# DM1092_IMU.net
KiCad netlist of a schematic drawn in Altium Designer
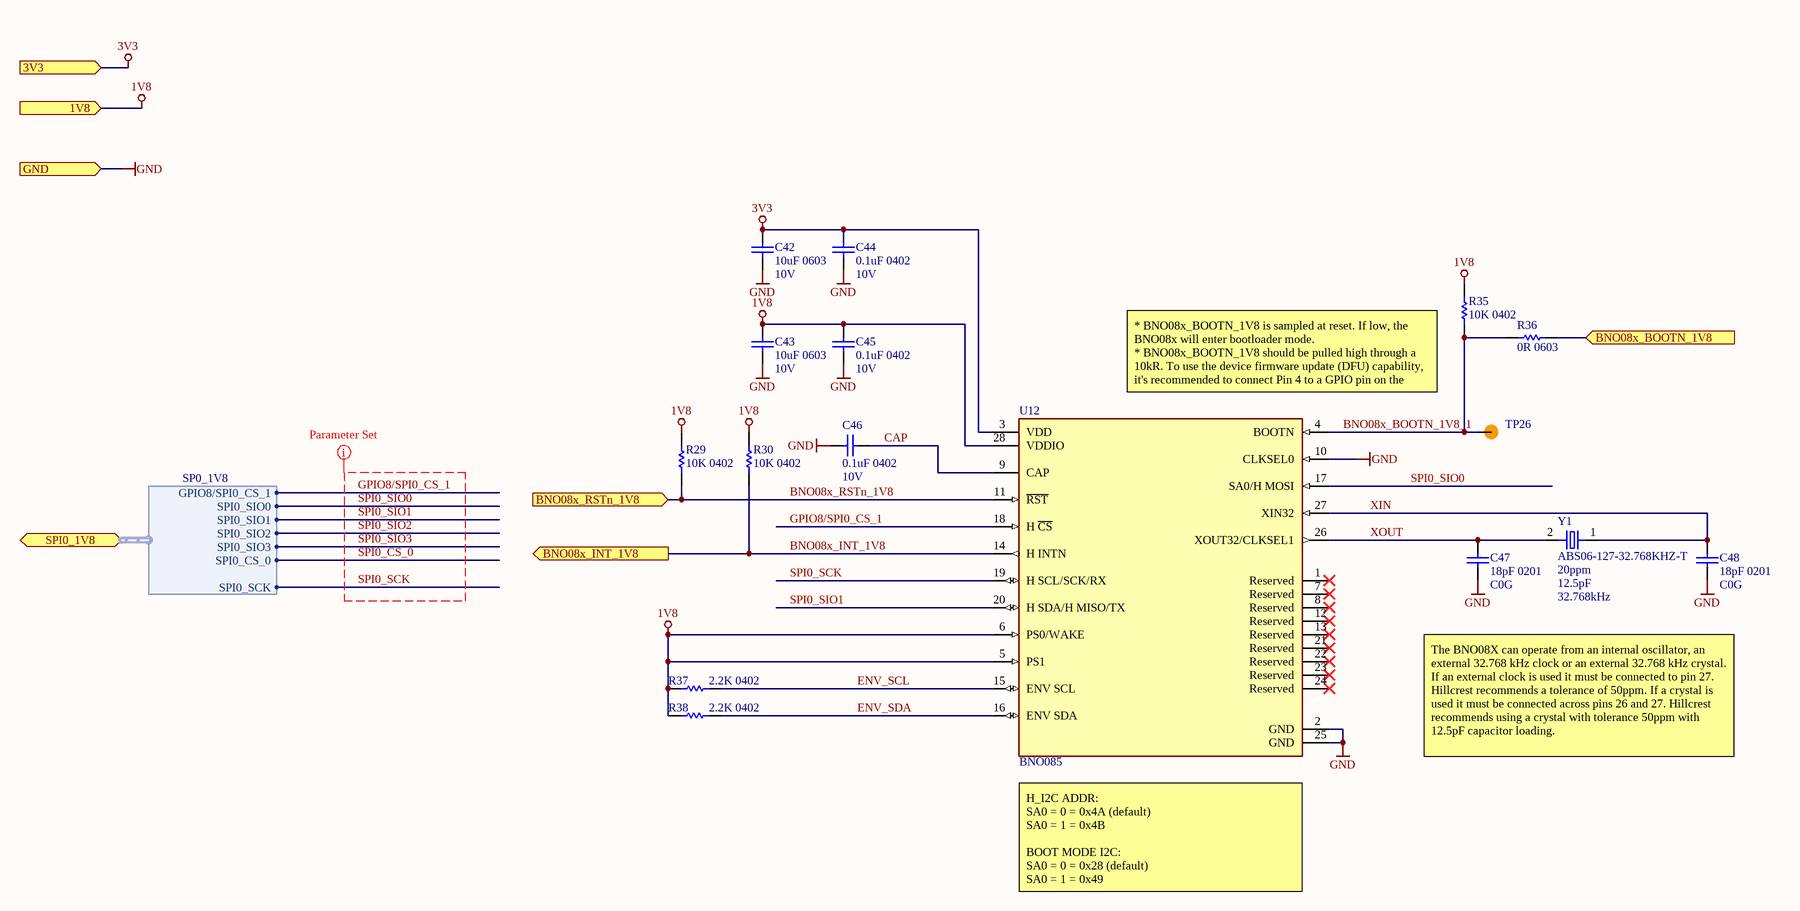
[diagram p0: DM1092_IMU.SchDoc]

(export (version "E")
  (design (tool "Eeschema 10.0.6"))
  (components
    (comp (ref "C42")
      (value "10uF 0603")
      (footprint "CAP_Altium_Vault_Generic:CAPC0603(1608)100_N")
      (description "CAP CER 10UF 10V X5R 0603 20%")
      (fields (field (name "TOLERANCE") "20%") (field (name "VOLTAGE RATING") "10V"))
      (libsource (lib "LuxonisMaster") (part "GRM188R61A106ME69D"))
    )
    (comp (ref "C43")
      (value "10uF 0603")
      (footprint "CAP_Altium_Vault_Generic:CAPC0603(1608)100_N")
      (description "CAP CER 10UF 10V X5R 0603 20%")
      (fields (field (name "TOLERANCE") "20%") (field (name "VOLTAGE RATING") "10V"))
      (libsource (lib "LuxonisMaster") (part "GRM188R61A106ME69D"))
    )
    (comp (ref "C44")
      (value "0.1uF 0402")
      (footprint "CAP_Altium_Vault_Generic:CAPC0402(1005)70_N")
      (description "CAP CER 0.1UF 10V X7R 0402 5%")
      (fields (field (name "TOLERANCE") "5%") (field (name "VOLTAGE RATING") "10V"))
      (libsource (lib "LuxonisMaster") (part "GRM155R71A104JA01D"))
    )
    (comp (ref "C45")
      (value "0.1uF 0402")
      (footprint "CAP_Altium_Vault_Generic:CAPC0402(1005)70_N")
      (description "CAP CER 0.1UF 10V X7R 0402 5%")
      (fields (field (name "TOLERANCE") "5%") (field (name "VOLTAGE RATING") "10V"))
      (libsource (lib "LuxonisMaster") (part "GRM155R71A104JA01D"))
    )
    (comp (ref "C46")
      (value "0.1uF 0402")
      (footprint "CAP_Altium_Vault_Generic:CAPC0402(1005)70_N")
      (description "CAP CER 0.1UF 10V X7R 0402 5%")
      (fields (field (name "TOLERANCE") "5%") (field (name "VOLTAGE RATING") "10V"))
      (libsource (lib "LuxonisMaster") (part "GRM155R71A104JA01D"))
    )
    (comp (ref "C47")
      (value "18pF 0201")
      (footprint "CAP_Altium_Vault_Generic:CAPC0201(0603)33_N")
      (description "Cap Ceramic 18pF 25V C0G 1% Pad SMD 0201 125C T/R")
      (fields (field (name "TOLERANCE") "1%") (field (name "DIELECTRIC") "C0G"))
      (libsource (lib "DM1092_R0M0E0") (part "GRM0335C1E180FA01D"))
    )
    (comp (ref "C48")
      (value "18pF 0201")
      (footprint "CAP_Altium_Vault_Generic:CAPC0201(0603)33_N")
      (description "Cap Ceramic 18pF 25V C0G 1% Pad SMD 0201 125C T/R")
      (fields (field (name "TOLERANCE") "1%") (field (name "DIELECTRIC") "C0G"))
      (libsource (lib "DM1092_R0M0E0") (part "GRM0335C1E180FA01D"))
    )
    (comp (ref "R29")
      (value "10K 0402")
      (footprint "RES_Altium_Vault_Generic:RESC0402(1005)_N")
      (fields (field (name "TOLERANCE") "1%"))
      (libsource (lib "LuxonisMaster") (part "RC0402FR-1310KL"))
    )
    (comp (ref "R30")
      (value "10K 0402")
      (footprint "RES_Altium_Vault_Generic:RESC0402(1005)_N")
      (fields (field (name "TOLERANCE") "1%"))
      (libsource (lib "LuxonisMaster") (part "RC0402FR-1310KL"))
    )
    (comp (ref "R35")
      (value "10K 0402")
      (footprint "RES_Altium_Vault_Generic:RESC0402(1005)_N")
      (fields (field (name "TOLERANCE") "1%"))
      (libsource (lib "LuxonisMaster") (part "RC0402FR-1310KL"))
    )
    (comp (ref "R36")
      (value "0R 0603")
      (footprint "RES_Altium_Vault_Generic:RESC0603(1608)_N")
      (fields (field (name "TOLERANCE") "5%"))
      (libsource (lib "LuxonisMaster") (part "CRCW06030000Z0EA"))
    )
    (comp (ref "R37")
      (value "2.2K 0402")
      (footprint "RES_Altium_Vault_Generic:RESC0402(1005)_N")
      (description "RES SMD 2.2K OHM 1% 1/16W 0402")
      (fields (field (name "TOLERANCE") "1%"))
      (libsource (lib "LuxonisMaster") (part "RC0402FR-072K2L"))
    )
    (comp (ref "R38")
      (value "2.2K 0402")
      (footprint "RES_Altium_Vault_Generic:RESC0402(1005)_N")
      (description "RES SMD 2.2K OHM 1% 1/16W 0402")
      (fields (field (name "TOLERANCE") "1%"))
      (libsource (lib "LuxonisMaster") (part "RC0402FR-072K2L"))
    )
    (comp (ref "TP26")
      (value "TP100_200_NS")
      (footprint "LuxonisMaster:TP100_200_NS")
      (libsource (lib "LuxonisMaster") (part "TEST_POINT"))
    )
    (comp (ref "U12")
      (value "BNO085")
      (footprint "BW1092_R0M0E0:BNO085")
      (description "IMU ACCEL/GYRO/MAG I2C 32BIT")
      (libsource (lib "DM1092_R0M0E0") (part "BNO085"))
    )
    (comp (ref "Y1")
      (value "ABS06-127-32.768KHZ-T")
      (footprint "BW1092_R0M0E0:ABS06-127-32.768KHZ-T")
      (description "CRYSTAL 32.768kHz ±20ppm Crystal 12.5pF 90 kOhms 2-SMD, No Lead")
      (fields
        (field (name "FREQUENCY TOLERANCE") "20ppm")
        (field (name "LOAD CAPACITANCE") "12.5pF")
        (field (name "FREQUENCY") "32.768kHz")
      )
      (libsource (lib "DM1092_R0M0E0") (part "ABS06-127-32.768KHZ-T"))
    )
  )
  (nets
    (net (code "2") (name "/BNO08x_BOOTN_1V8") (class "Default")
      (node (ref "R36") (pin "2") (pinfunction "2_2") (pintype "passive"))
    )
    (net (code "3") (name "/BNO08x_BOOTN_1V8_1") (class "Default")
      (node (ref "R35") (pin "1") (pinfunction "1_1") (pintype "passive"))
      (node (ref "R36") (pin "1") (pinfunction "1_1") (pintype "passive"))
      (node (ref "TP26") (pin "1") (pintype "passive"))
      (node (ref "U12") (pin "4") (pinfunction "BOOTN_4") (pintype "input"))
    )
    (net (code "4") (name "/BNO08x_INT_1V8") (class "Default")
      (node (ref "R30") (pin "1") (pinfunction "1_1") (pintype "passive"))
      (node (ref "U12") (pin "14") (pinfunction "H_INTN_14") (pintype "output"))
    )
    (net (code "5") (name "/BNO08x_RSTn_1V8") (class "Default")
      (node (ref "R29") (pin "1") (pinfunction "1_1") (pintype "passive"))
      (node (ref "U12") (pin "11") (pinfunction "~{RST}_11") (pintype "input"))
    )
    (net (code "6") (name "/CAP") (class "Default")
      (node (ref "C46") (pin "1") (pinfunction "1_1") (pintype "passive"))
      (node (ref "U12") (pin "9") (pinfunction "CAP_9") (pintype "passive"))
    )
    (net (code "7") (name "/ENV_SCL") (class "Default")
      (node (ref "R37") (pin "2") (pinfunction "2_2") (pintype "passive"))
      (node (ref "U12") (pin "15") (pinfunction "ENV_SCL_15") (pintype "bidirectional"))
    )
    (net (code "8") (name "/ENV_SDA") (class "Default")
      (node (ref "R38") (pin "2") (pinfunction "2_2") (pintype "passive"))
      (node (ref "U12") (pin "16") (pinfunction "ENV_SDA_16") (pintype "bidirectional"))
    )
    (net (code "9") (name "/GPIO8{slash}SPI0_CS_1") (class "Default")
      (node (ref "U12") (pin "18") (pinfunction "H_~{CS}_18") (pintype "input"))
    )
    (net (code "11") (name "/SPI0_SCK") (class "Default")
      (node (ref "U12") (pin "19") (pinfunction "H_SCL/SCK/RX_19") (pintype "bidirectional"))
    )
    (net (code "12") (name "/SPI0_SIO0") (class "Default")
      (node (ref "U12") (pin "17") (pinfunction "SA0/H_MOSI_17") (pintype "input"))
    )
    (net (code "13") (name "/SPI0_SIO1") (class "Default")
      (node (ref "U12") (pin "20") (pinfunction "H_SDA/H_MISO/TX_20") (pintype "bidirectional"))
    )
    (net (code "16") (name "/XIN") (class "Default")
      (node (ref "C48") (pin "2") (pinfunction "2_2") (pintype "passive"))
      (node (ref "U12") (pin "27") (pinfunction "XIN32_27") (pintype "input"))
      (node (ref "Y1") (pin "1") (pinfunction "1_1") (pintype "passive"))
    )
    (net (code "17") (name "/XOUT") (class "Default")
      (node (ref "C47") (pin "2") (pinfunction "2_2") (pintype "passive"))
      (node (ref "U12") (pin "26") (pinfunction "XOUT32/CLKSEL1_26") (pintype "output"))
      (node (ref "Y1") (pin "2") (pinfunction "2_2") (pintype "passive"))
    )
    (net (code "19") (name "1V8") (class "Default")
      (node (ref "C43") (pin "2") (pinfunction "2_2") (pintype "passive"))
      (node (ref "C45") (pin "2") (pinfunction "2_2") (pintype "passive"))
      (node (ref "R29") (pin "2") (pinfunction "2_2") (pintype "passive"))
      (node (ref "R30") (pin "2") (pinfunction "2_2") (pintype "passive"))
      (node (ref "R35") (pin "2") (pinfunction "2_2") (pintype "passive"))
      (node (ref "R37") (pin "1") (pinfunction "1_1") (pintype "passive"))
      (node (ref "R38") (pin "1") (pinfunction "1_1") (pintype "passive"))
      (node (ref "U12") (pin "28") (pinfunction "VDDIO_28") (pintype "power_in"))
      (node (ref "U12") (pin "5") (pinfunction "PS1_5") (pintype "input"))
      (node (ref "U12") (pin "6") (pinfunction "PS0/WAKE_6") (pintype "input"))
    )
    (net (code "20") (name "3V3") (class "Default")
      (node (ref "C42") (pin "2") (pinfunction "2_2") (pintype "passive"))
      (node (ref "C44") (pin "2") (pinfunction "2_2") (pintype "passive"))
      (node (ref "U12") (pin "3") (pinfunction "VDD_3") (pintype "power_in"))
    )
    (net (code "21") (name "GND") (class "Default")
      (node (ref "C42") (pin "1") (pinfunction "1_1") (pintype "passive"))
      (node (ref "C43") (pin "1") (pinfunction "1_1") (pintype "passive"))
      (node (ref "C44") (pin "1") (pinfunction "1_1") (pintype "passive"))
      (node (ref "C45") (pin "1") (pinfunction "1_1") (pintype "passive"))
      (node (ref "C46") (pin "2") (pinfunction "2_2") (pintype "passive"))
      (node (ref "C47") (pin "1") (pinfunction "1_1") (pintype "passive"))
      (node (ref "C48") (pin "1") (pinfunction "1_1") (pintype "passive"))
      (node (ref "U12") (pin "10") (pinfunction "CLKSEL0_10") (pintype "input"))
      (node (ref "U12") (pin "2") (pinfunction "GND_2") (pintype "power_in"))
      (node (ref "U12") (pin "25") (pinfunction "GND_25") (pintype "power_in"))
    )
    (net (code "22") (name "unconnected-(U12-Reserved-Pad1)") (class "Default")
      (node (ref "U12") (pin "1") (pinfunction "Reserved_1") (pintype "passive+no_connect"))
    )
    (net (code "23") (name "unconnected-(U12-Reserved-Pad7)") (class "Default")
      (node (ref "U12") (pin "7") (pinfunction "Reserved_7") (pintype "passive+no_connect"))
    )
    (net (code "24") (name "unconnected-(U12-Reserved-Pad8)") (class "Default")
      (node (ref "U12") (pin "8") (pinfunction "Reserved_8") (pintype "passive+no_connect"))
    )
    (net (code "25") (name "unconnected-(U12-Reserved-Pad12)") (class "Default")
      (node (ref "U12") (pin "12") (pinfunction "Reserved_12") (pintype "passive+no_connect"))
    )
    (net (code "26") (name "unconnected-(U12-Reserved-Pad13)") (class "Default")
      (node (ref "U12") (pin "13") (pinfunction "Reserved_13") (pintype "passive+no_connect"))
    )
    (net (code "27") (name "unconnected-(U12-Reserved-Pad21)") (class "Default")
      (node (ref "U12") (pin "21") (pinfunction "Reserved_21") (pintype "passive+no_connect"))
    )
    (net (code "28") (name "unconnected-(U12-Reserved-Pad22)") (class "Default")
      (node (ref "U12") (pin "22") (pinfunction "Reserved_22") (pintype "passive+no_connect"))
    )
    (net (code "29") (name "unconnected-(U12-Reserved-Pad23)") (class "Default")
      (node (ref "U12") (pin "23") (pinfunction "Reserved_23") (pintype "passive+no_connect"))
    )
    (net (code "30") (name "unconnected-(U12-Reserved-Pad24)") (class "Default")
      (node (ref "U12") (pin "24") (pinfunction "Reserved_24") (pintype "passive+no_connect"))
    )
  )
)
